# 3_0.net
KiCad netlist of a schematic drawn in EasyEDA
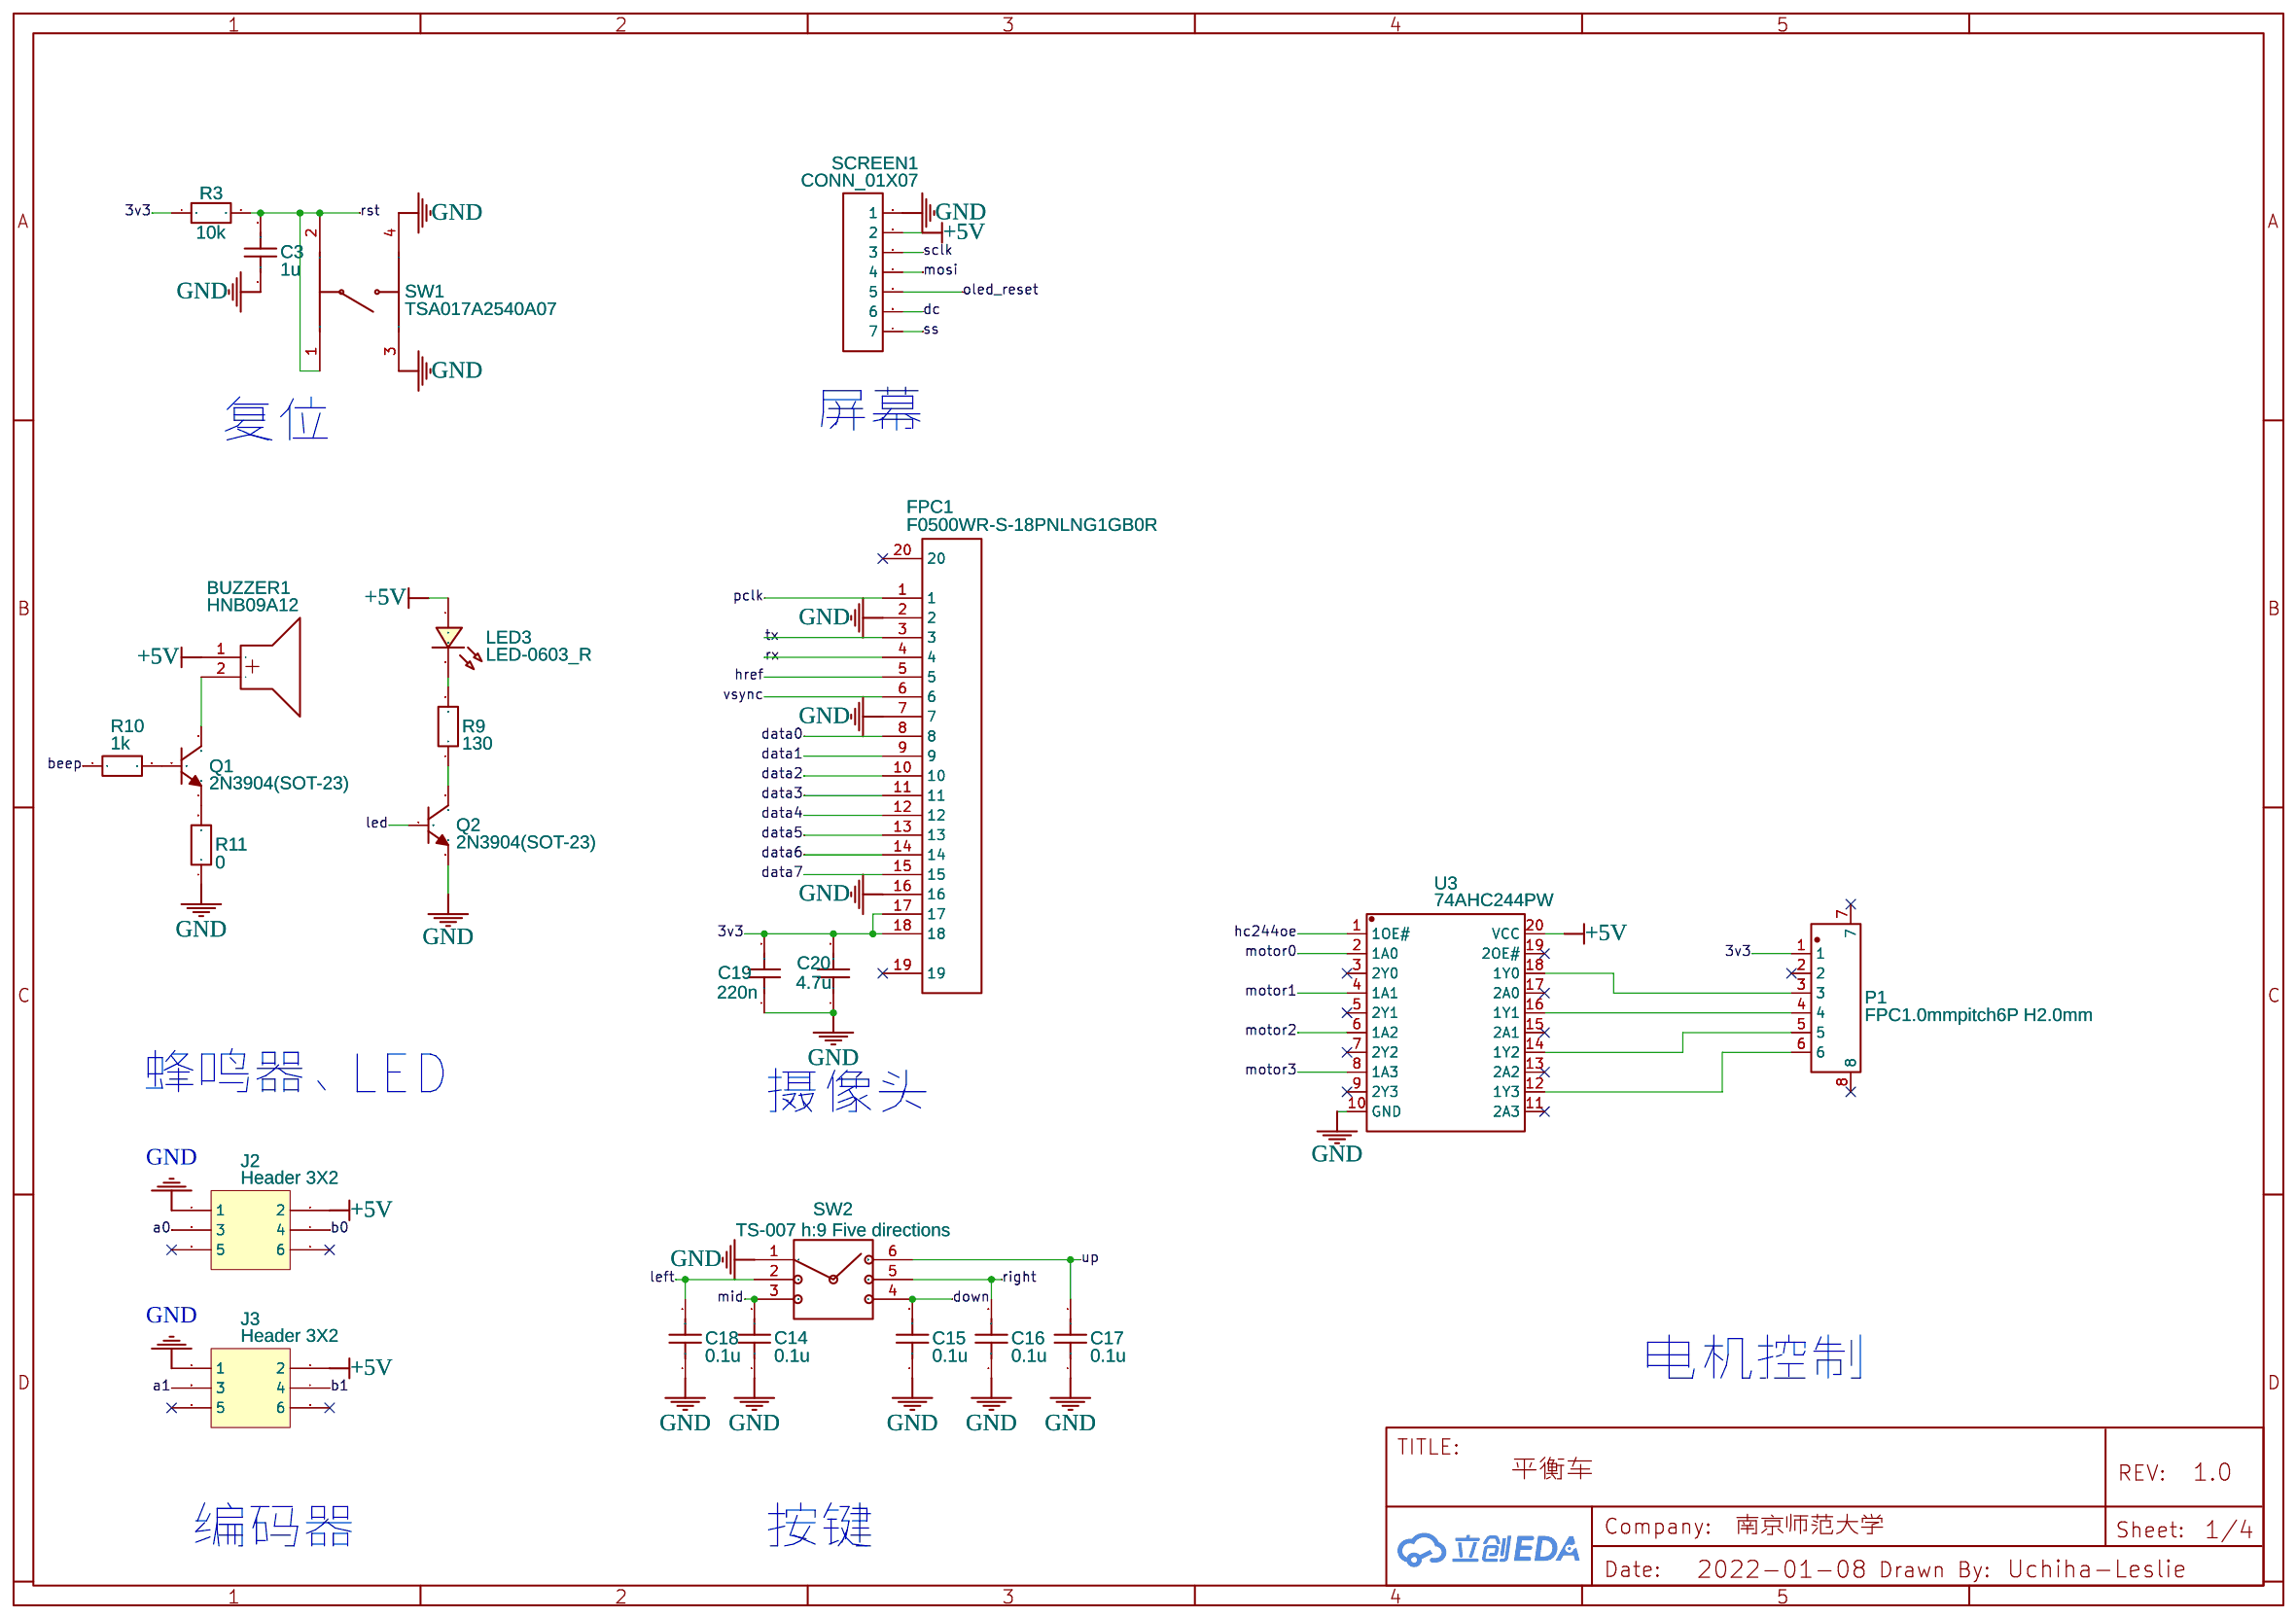
[diagram p0: Sheet_1]
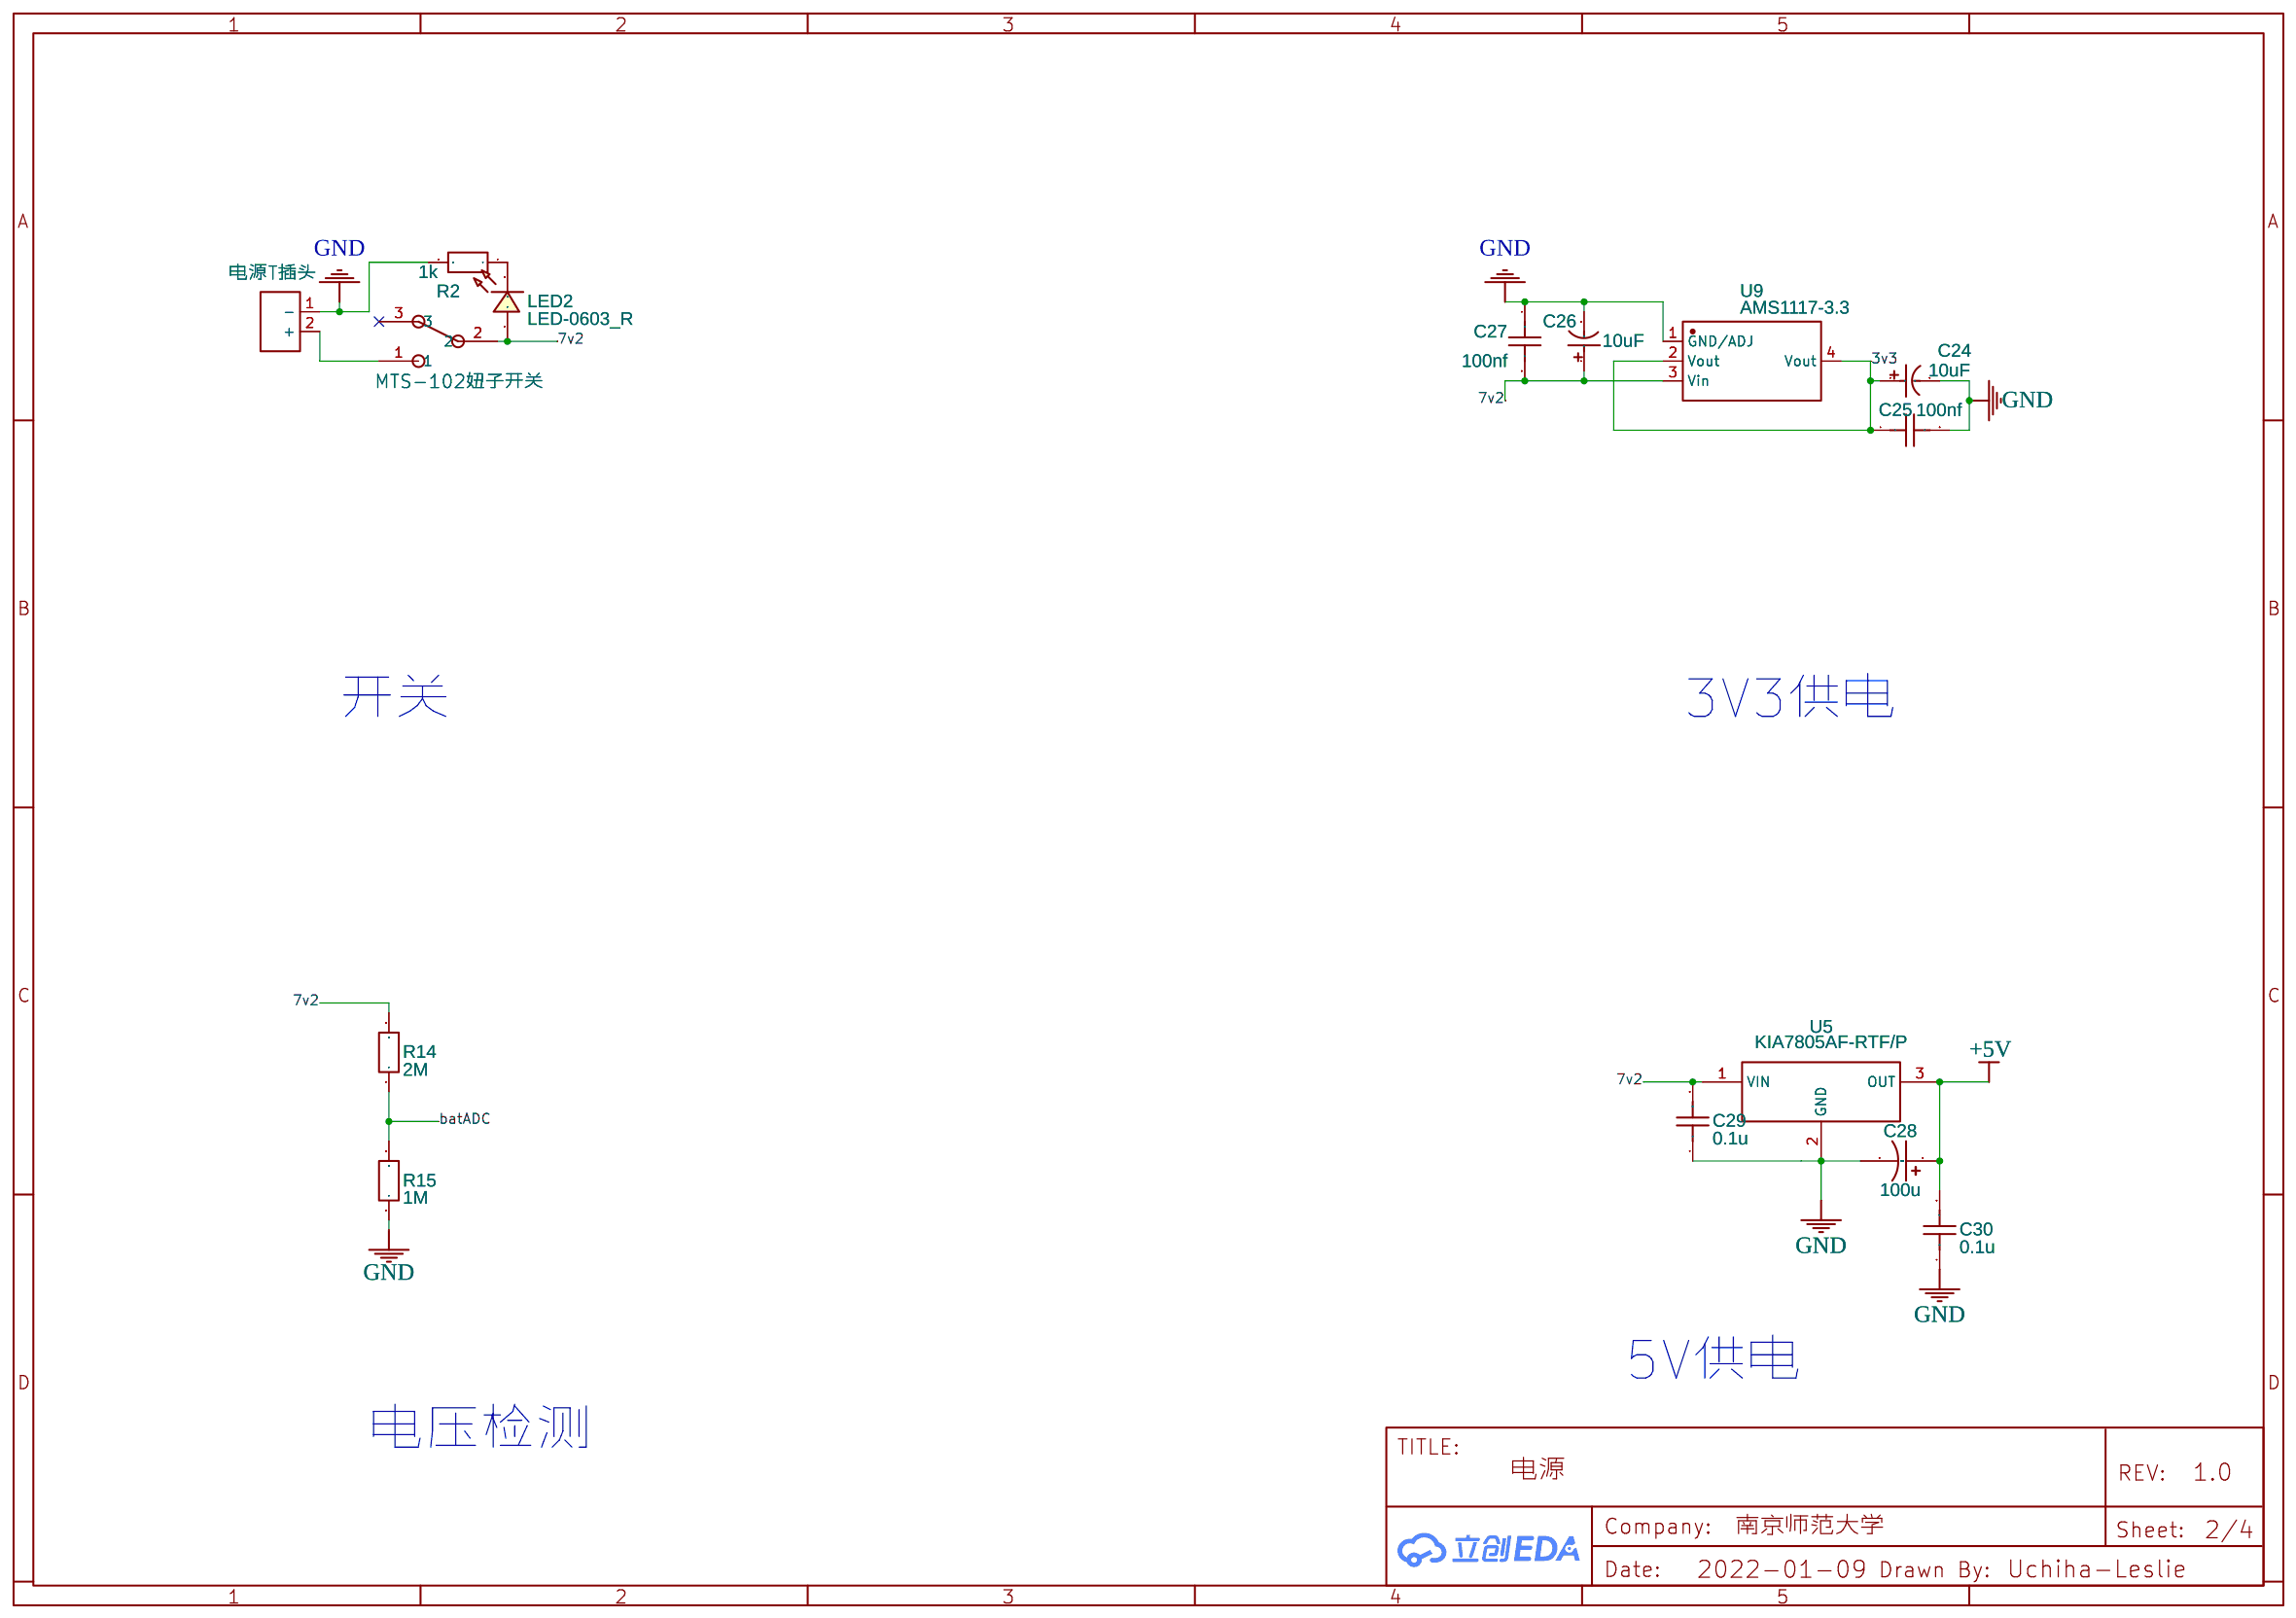
[diagram p1: 电源]
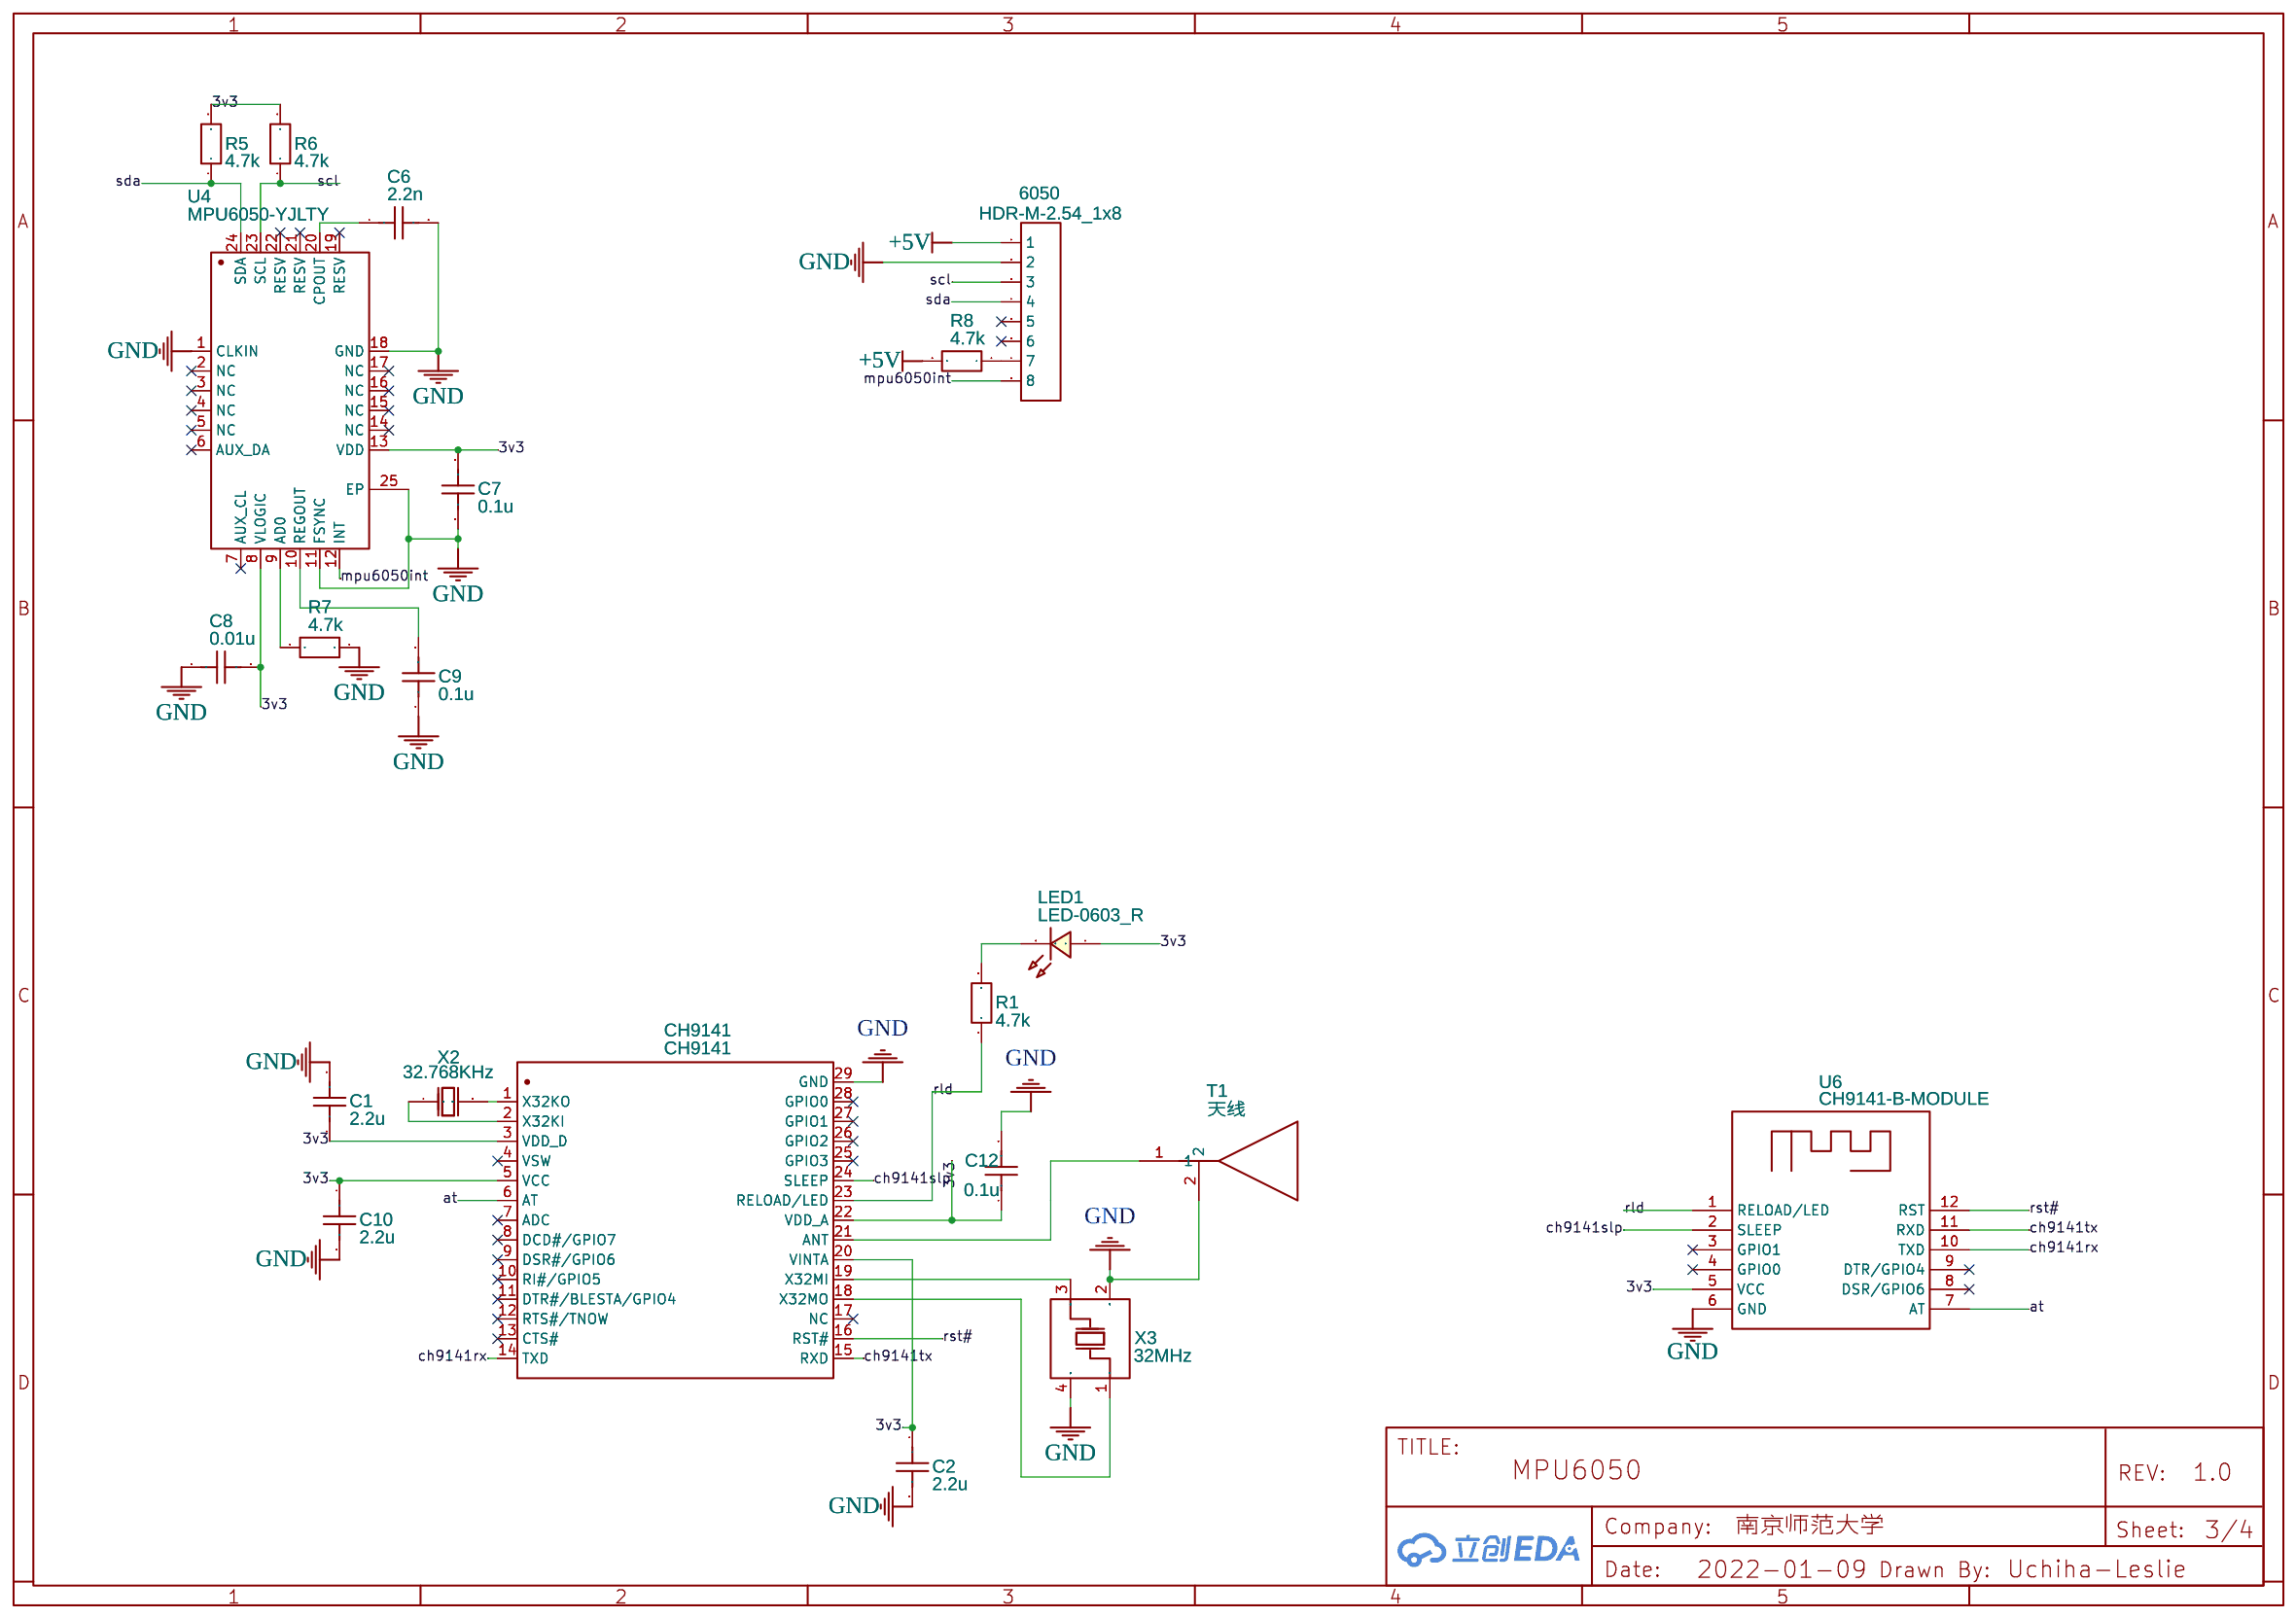
[diagram p2: MPU/蓝牙]
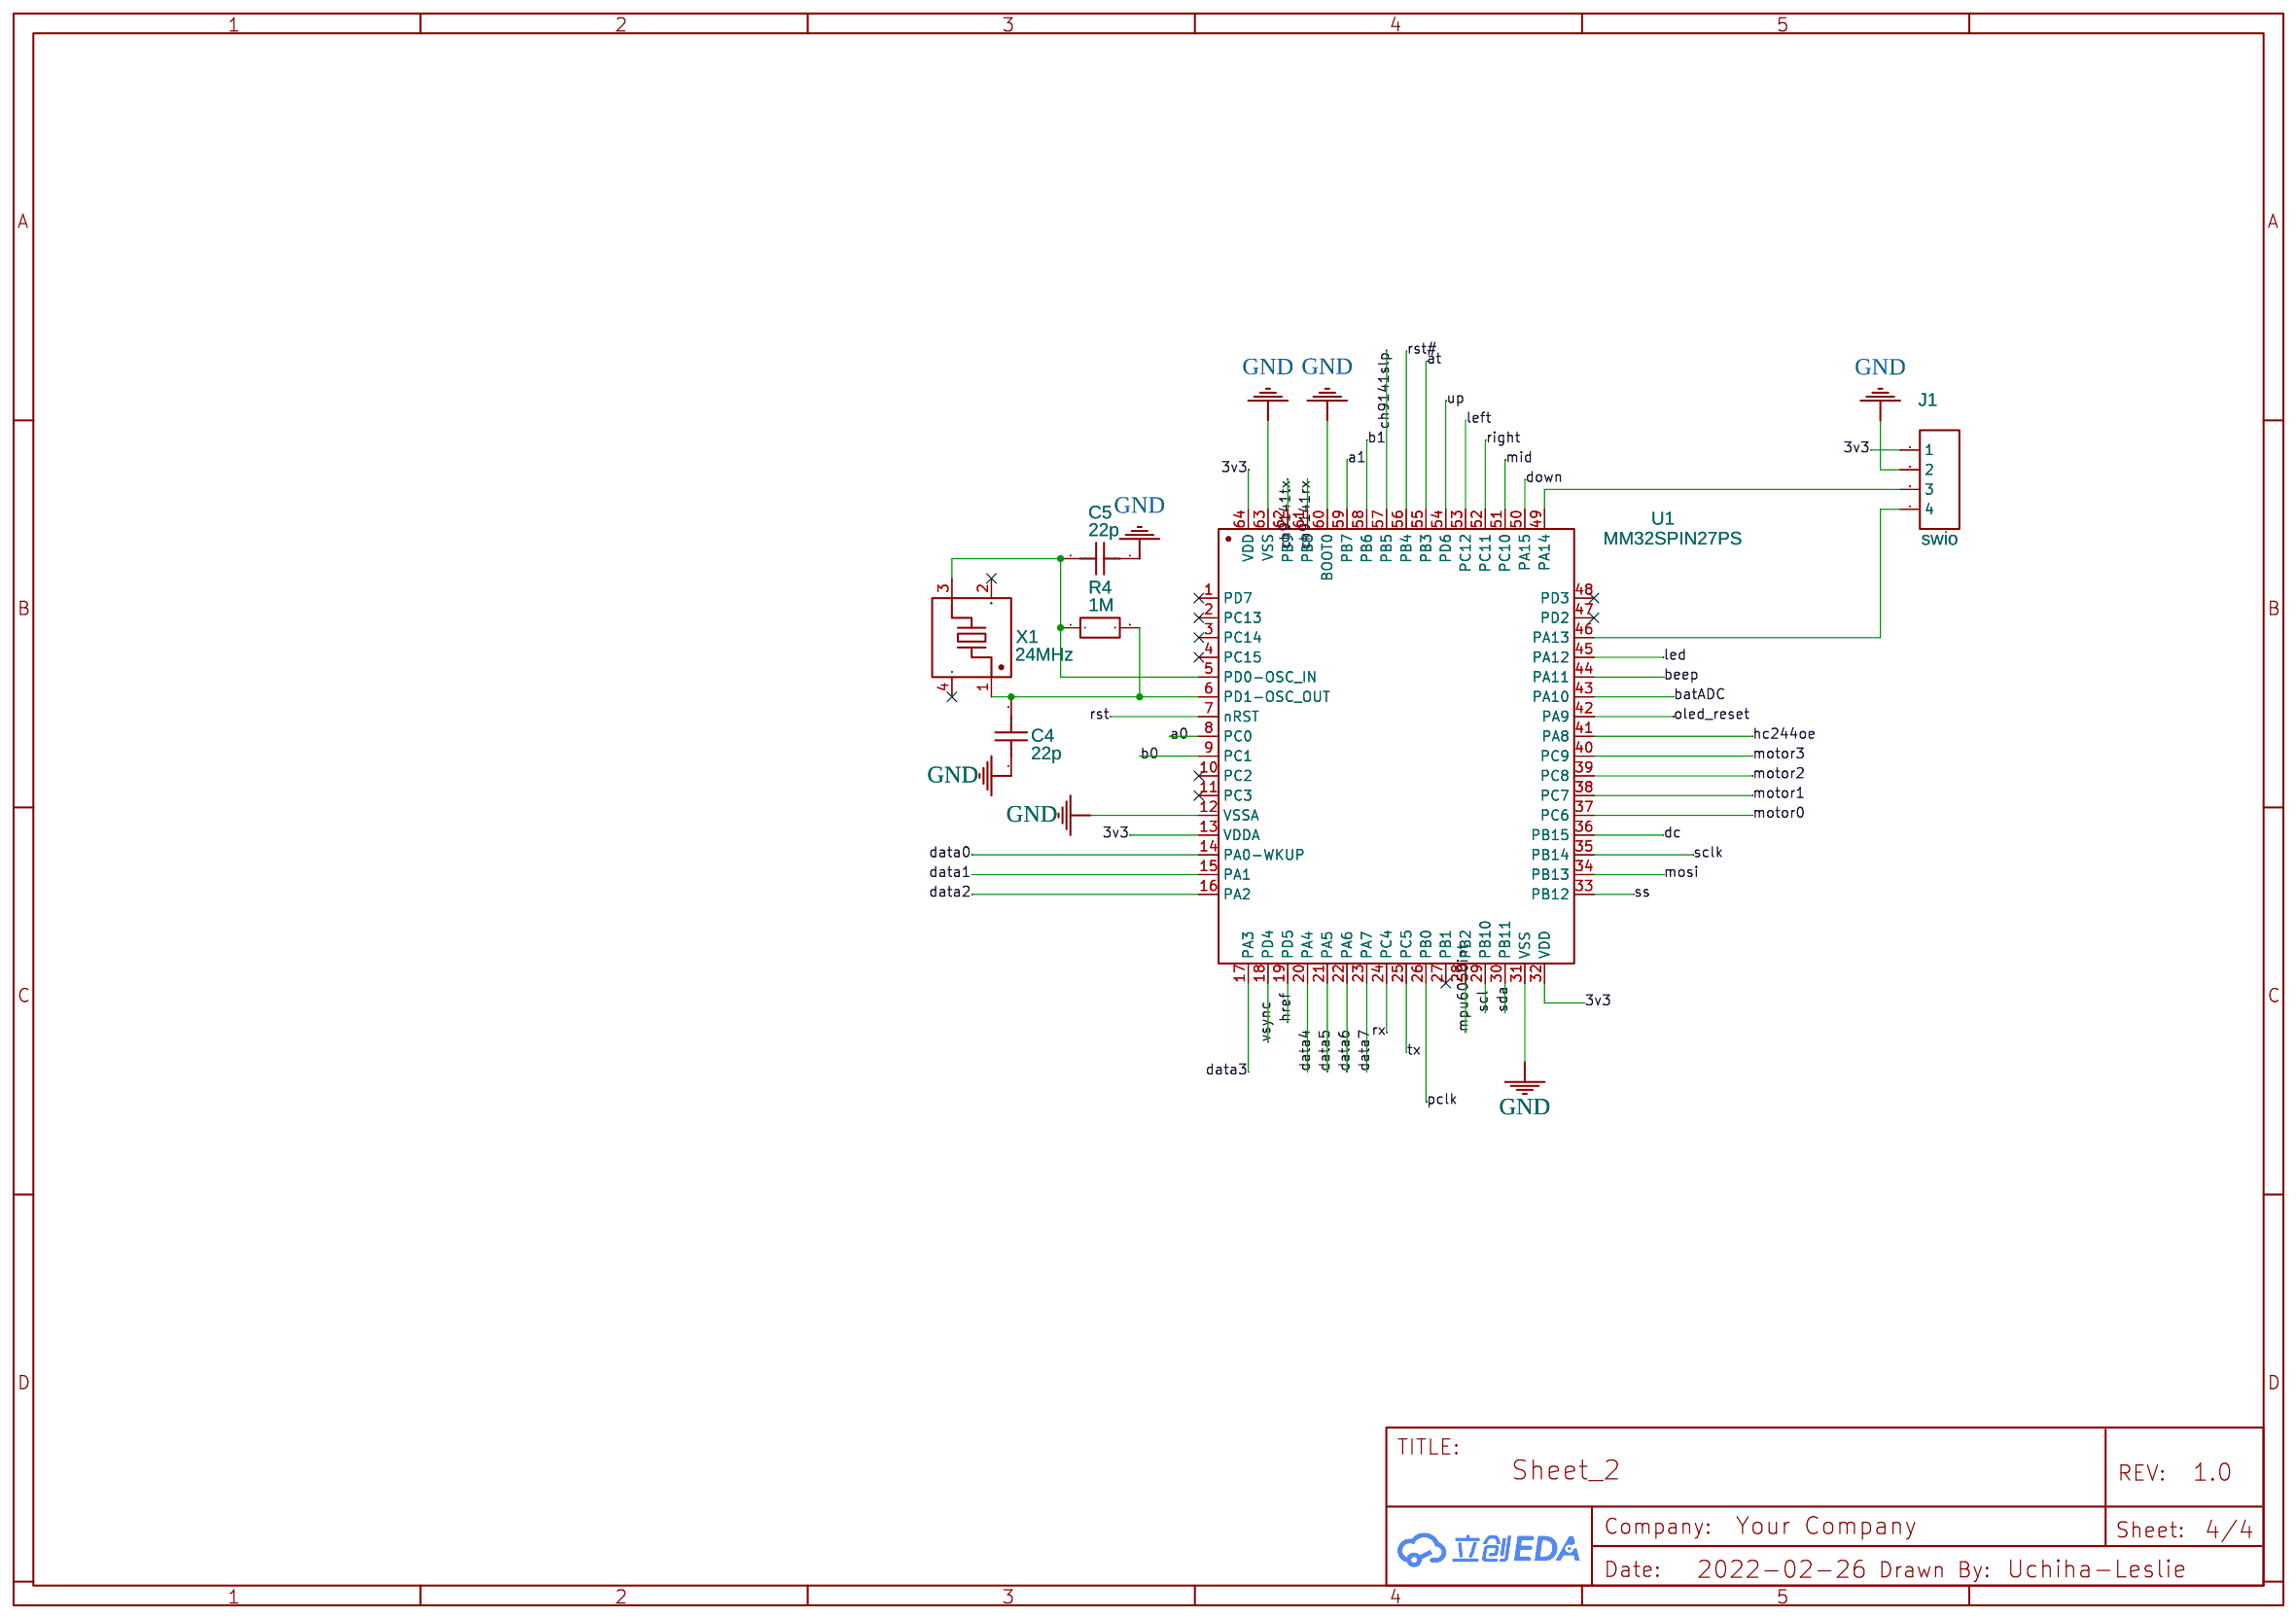
[diagram p3: MCU]

(export (version "E")
  (design (tool "Eeschema 10.0.6"))
  (components
    (comp (ref "BUZZER1")
      (value "HNB09A12")
      (fields (field (name "BOM_Supplier Part") "C122600"))
      (libsource (lib "") (part "HNB09A12"))
    )
    (comp (ref "C3") (value "1u") (libsource (lib "") (part "C_0603_US")))
    (comp (ref "C14") (value "0.1u") (libsource (lib "") (part "C_0603_US")))
    (comp (ref "C15") (value "0.1u") (libsource (lib "") (part "C_0603_US")))
    (comp (ref "C16") (value "0.1u") (libsource (lib "") (part "C_0603_US")))
    (comp (ref "C17") (value "0.1u") (libsource (lib "") (part "C_0603_US")))
    (comp (ref "C18") (value "0.1u") (libsource (lib "") (part "C_0603_US")))
    (comp (ref "C19") (value "220n") (libsource (lib "") (part "C_0603_US")))
    (comp (ref "C20") (value "4.7u") (libsource (lib "") (part "C_0603_US")))
    (comp (ref "FPC1")
      (value "F0500WR-S-18PNLNG1GB0R")
      (fields (field (name "BOM_Supplier Part") "C247896"))
      (libsource (lib "") (part "F0500WR-S-18PNLNG1GB0R"))
    )
    (comp (ref "J2") (value "Header 3X2") (libsource (lib "") (part "Header 3X2")))
    (comp (ref "J3") (value "Header 3X2") (libsource (lib "") (part "Header 3X2")))
    (comp (ref "LED3")
      (value "LED-0603_R")
      (fields
        (field (name "BOM_Manufacturer Part") "19-217/R6C-AL1M2VY/3T")
        (field (name "BOM_Supplier Part") "C72044")
      )
      (libsource (lib "") (part "LED-0603_R"))
    )
    (comp (ref "P1")
      (value "FPC1.0mmpitch6P H2.0mm")
      (fields
        (field (name "BOM_Manufacturer Part") "FPC1.0mmpitch6P H2.0mm翻盖式下接式")
        (field (name "BOM_Supplier Part") "C29804")
      )
      (libsource (lib "") (part "FPC1.0mmpitch6P H2.0mm"))
    )
    (comp (ref "Q1")
      (value "2N3904(SOT-23)")
      (fields
        (field (name "BOM_Manufacturer Part") "2n3904S-RTK/PS")
        (field (name "BOM_Supplier Part") "C18536")
      )
      (libsource (lib "") (part "2N3904(SOT-23)"))
    )
    (comp (ref "Q2")
      (value "2N3904(SOT-23)")
      (fields
        (field (name "BOM_Manufacturer Part") "2n3904S-RTK/PS")
        (field (name "BOM_Supplier Part") "C18536")
      )
      (libsource (lib "") (part "2N3904(SOT-23)"))
    )
    (comp (ref "R3") (value "10k") (libsource (lib "") (part "R_0603_EU")))
    (comp (ref "R9") (value "130") (libsource (lib "") (part "R_0603_EU_1")))
    (comp (ref "R10") (value "1k") (libsource (lib "") (part "R_0603_EU")))
    (comp (ref "R11") (value "0") (libsource (lib "") (part "R_0603_EU_1")))
    (comp (ref "SCREEN1") (value "CONN_01X07") (libsource (lib "") (part "CONN_01X07")))
    (comp (ref "SW1")
      (value "TSA017A2540A07")
      (fields (field (name "BOM_Supplier Part") "C2888434"))
      (libsource (lib "") (part "TSA017A2540A07"))
    )
    (comp (ref "SW2")
      (value "TS-007 h:9 Five directions")
      (fields (field (name "BOM_Supplier Part") "C3679"))
      (libsource (lib "") (part "TS-007 h{colon}9 Five directions"))
    )
    (comp (ref "U3")
      (value "74AHC244PW")
      (fields (field (name "BOM_Supplier Part") "C5515"))
      (libsource (lib "") (part "74AHC244PW"))
    )
    (comp (ref "C24")
      (value "10uF")
      (fields
        (field (name "BOM_Manufacturer Part") "10uF 16V 3*5")
        (field (name "BOM_Supplier Part") "C43798")
      )
      (libsource (lib "") (part "10uF 16V 3*5_1"))
    )
    (comp (ref "C25") (value "100nf") (libsource (lib "") (part "C_0603_US_2")))
    (comp (ref "C26")
      (value "10uF")
      (fields
        (field (name "BOM_Manufacturer Part") "10uF 16V 3*5")
        (field (name "BOM_Supplier Part") "C43798")
      )
      (libsource (lib "") (part "10uF 16V 3*5"))
    )
    (comp (ref "C27") (value "100nf") (libsource (lib "") (part "C_0603_US")))
    (comp (ref "C28") (value "100u") (libsource (lib "") (part "CE_TH_D8.0×F3.5_US")))
    (comp (ref "C29") (value "0.1u") (libsource (lib "") (part "C_0603_US_1")))
    (comp (ref "C30") (value "0.1u") (libsource (lib "") (part "C_0603_US_1")))
    (comp (ref "H1")
      (value "电源T插头")
      (fields (field (name "BOM_Manufacturer Part") "3-644456-2") (field (name "BOM_Supplier Part") "C90288"))
      (libsource (lib "") (part "电源T插头"))
    )
    (comp (ref "LED2")
      (value "LED-0603_R")
      (fields
        (field (name "BOM_Manufacturer Part") "19-217/R6C-AL1M2VY/3T")
        (field (name "BOM_Supplier Part") "C72044")
      )
      (libsource (lib "") (part "LED-0603_R"))
    )
    (comp (ref "R2") (value "1k") (libsource (lib "") (part "R_0603_EU")))
    (comp (ref "R14") (value "2M") (libsource (lib "") (part "R_0603_EU_1")))
    (comp (ref "R15") (value "1M") (libsource (lib "") (part "R_0603_EU_1")))
    (comp (ref "U2") (value "MTS-102妞子开关") (libsource (lib "") (part "MTS-102妞子开关")))
    (comp (ref "U5")
      (value "KIA7805AF-RTF/P")
      (fields (field (name "BOM_Supplier Part") "C69755"))
      (libsource (lib "") (part "KIA7805AF-RTF/P"))
    )
    (comp (ref "U9")
      (value "AMS1117-3.3")
      (fields (field (name "BOM_Supplier Part") "C6186"))
      (libsource (lib "") (part "AMS1117-3.3"))
    )
    (comp (ref "6050")
      (value "HDR-M-2.54_1x8")
      (fields (field (name "BOM_Supplier Part") "C190820"))
      (libsource (lib "") (part "HDR-M-2.54_1x8"))
    )
    (comp (ref "C1") (value "2.2u") (libsource (lib "") (part "C_0603_US")))
    (comp (ref "C2") (value "2.2u") (libsource (lib "") (part "C_0603_US_2")))
    (comp (ref "C6") (value "2.2n") (libsource (lib "") (part "C_0603_US_1")))
    (comp (ref "C7") (value "0.1u") (libsource (lib "") (part "C_0603_US")))
    (comp (ref "C8") (value "0.01u") (libsource (lib "") (part "C_0603_US_1")))
    (comp (ref "C9") (value "0.1u") (libsource (lib "") (part "C_0603_US")))
    (comp (ref "C10") (value "2.2u") (libsource (lib "") (part "C_0603_US_2")))
    (comp (ref "C12") (value "0.1u") (libsource (lib "") (part "C_0603_US")))
    (comp (ref "CH9141")
      (value "CH9141")
      (fields (field (name "BOM_Supplier Part") "C2693433"))
      (libsource (lib "") (part "CH9141"))
    )
    (comp (ref "LED1")
      (value "LED-0603_R")
      (fields
        (field (name "BOM_Manufacturer Part") "19-217/R6C-AL1M2VY/3T")
        (field (name "BOM_Supplier Part") "C72044")
      )
      (libsource (lib "") (part "LED-0603_R"))
    )
    (comp (ref "R1") (value "4.7k") (libsource (lib "") (part "R_0603_EU_1")))
    (comp (ref "R5") (value "4.7k") (libsource (lib "") (part "R_0603_EU_1")))
    (comp (ref "R6") (value "4.7k") (libsource (lib "") (part "R_0603_EU_1")))
    (comp (ref "R7") (value "4.7k") (libsource (lib "") (part "R_0603_EU")))
    (comp (ref "R8") (value "4.7k") (libsource (lib "") (part "R_0603_EU")))
    (comp (ref "T1") (value "天线") (libsource (lib "") (part "天线")))
    (comp (ref "U4")
      (value "MPU6050-YJLTY")
      (fields (field (name "BOM_Supplier Part") "C2912107"))
      (libsource (lib "") (part "MPU6050-YJLTY"))
    )
    (comp (ref "U6") (value "CH9141-B-MODULE") (libsource (lib "") (part "CH9141-B-MODULE")))
    (comp (ref "X2")
      (value "32.768KHz")
      (fields
        (field (name "BOM_Manufacturer Part") "ABS07-32.768KHZ-9-T")
        (field (name "BOM_Supplier Part") "C179635")
      )
      (libsource (lib "") (part "ABS07-32.768KHZ-9-T"))
    )
    (comp (ref "X3")
      (value "32MHz")
      (fields
        (field (name "BOM_Manufacturer Part") "M32000TC142")
        (field (name "BOM_Supplier Part") "C280076")
      )
      (libsource (lib "") (part "M32000TC142"))
    )
    (comp (ref "C4") (value "22p") (libsource (lib "") (part "C_0603_US_1")))
    (comp (ref "C5") (value "22p") (libsource (lib "") (part "C_0603_US")))
    (comp (ref "J1")
      (value "swio")
      (fields (field (name "BOM_Supplier Part") "C124378"))
      (libsource (lib "") (part "HDR-M-2.54_1x4"))
    )
    (comp (ref "R4") (value "1M") (libsource (lib "") (part "R_0603_EU")))
    (comp (ref "U1")
      (value "MM32SPIN27PS")
      (fields
        (field (name "BOM_Manufacturer Part") "mm32spin27ps")
        (field (name "BOM_Supplier Part") "C2908053")
      )
      (libsource (lib "") (part "MM32SPIN27PS"))
    )
    (comp (ref "X1")
      (value "24MHz")
      (fields
        (field (name "BOM_Manufacturer Part") "CN4024M00012T8188012")
        (field (name "BOM_Supplier Part") "C708987")
      )
      (libsource (lib "") (part "CN4024M00012T8188012"))
    )
  )
  (nets
    (net (code "1") (name "+5V") (class "Default")
      (node (ref "6050") (pin "1") (pinfunction "1_1") (pintype "unspecified"))
      (node (ref "BUZZER1") (pin "1") (pinfunction "+_1") (pintype "unspecified"))
      (node (ref "C28") (pin "1") (pinfunction "1_1") (pintype "unspecified"))
      (node (ref "C30") (pin "2") (pinfunction "2_2") (pintype "unspecified"))
      (node (ref "J2") (pin "2") (pinfunction "2_2") (pintype "unspecified"))
      (node (ref "J3") (pin "2") (pinfunction "2_2") (pintype "unspecified"))
      (node (ref "LED3") (pin "1") (pinfunction "1_1") (pintype "unspecified"))
      (node (ref "R8") (pin "2") (pinfunction "2_2") (pintype "unspecified"))
      (node (ref "SCREEN1") (pin "2") (pinfunction "2_2") (pintype "input"))
      (node (ref "U3") (pin "20") (pinfunction "VCC_20") (pintype "unspecified"))
      (node (ref "U5") (pin "3") (pinfunction "OUT_3") (pintype "unspecified"))
    )
    (net (code "2") (name "3v3") (class "Default")
      (node (ref "C1") (pin "1") (pinfunction "1_1") (pintype "unspecified"))
      (node (ref "C10") (pin "1") (pinfunction "1_1") (pintype "unspecified"))
      (node (ref "C12") (pin "1") (pinfunction "1_1") (pintype "unspecified"))
      (node (ref "C19") (pin "2") (pinfunction "2_2") (pintype "unspecified"))
      (node (ref "C2") (pin "1") (pinfunction "1_1") (pintype "unspecified"))
      (node (ref "C20") (pin "2") (pinfunction "2_2") (pintype "unspecified"))
      (node (ref "C24") (pin "1") (pinfunction "1_1") (pintype "input"))
      (node (ref "C25") (pin "1") (pinfunction "1_1") (pintype "unspecified"))
      (node (ref "C7") (pin "2") (pinfunction "2_2") (pintype "unspecified"))
      (node (ref "C8") (pin "2") (pinfunction "2_2") (pintype "unspecified"))
      (node (ref "CH9141") (pin "20") (pinfunction "VINTA_20") (pintype "unspecified"))
      (node (ref "CH9141") (pin "22") (pinfunction "VDD_A_22") (pintype "unspecified"))
      (node (ref "CH9141") (pin "3") (pinfunction "VDD_D_3") (pintype "unspecified"))
      (node (ref "CH9141") (pin "5") (pinfunction "VCC_5") (pintype "unspecified"))
      (node (ref "FPC1") (pin "17") (pinfunction "17_17") (pintype "unspecified"))
      (node (ref "FPC1") (pin "18") (pinfunction "18_18") (pintype "unspecified"))
      (node (ref "J1") (pin "1") (pinfunction "1_1") (pintype "unspecified"))
      (node (ref "LED1") (pin "1") (pinfunction "1_1") (pintype "unspecified"))
      (node (ref "P1") (pin "1") (pinfunction "1_1") (pintype "unspecified"))
      (node (ref "R3") (pin "1") (pinfunction "1_1") (pintype "unspecified"))
      (node (ref "R5") (pin "2") (pinfunction "2_2") (pintype "unspecified"))
      (node (ref "R6") (pin "2") (pinfunction "2_2") (pintype "unspecified"))
      (node (ref "U1") (pin "13") (pinfunction "VDDA_13") (pintype "unspecified"))
      (node (ref "U1") (pin "32") (pinfunction "VDD_32") (pintype "unspecified"))
      (node (ref "U1") (pin "64") (pinfunction "VDD_64") (pintype "unspecified"))
      (node (ref "U4") (pin "13") (pinfunction "VDD_13") (pintype "unspecified"))
      (node (ref "U4") (pin "8") (pinfunction "VLOGIC_8") (pintype "unspecified"))
      (node (ref "U6") (pin "5") (pinfunction "VCC_5") (pintype "unspecified"))
      (node (ref "U9") (pin "2") (pinfunction "Vout_2") (pintype "unspecified"))
      (node (ref "U9") (pin "4") (pinfunction "Vout_4") (pintype "unspecified"))
    )
    (net (code "3") (name "7v2") (class "Default")
      (node (ref "C26") (pin "1") (pinfunction "1_1") (pintype "input"))
      (node (ref "C27") (pin "2") (pinfunction "2_2") (pintype "unspecified"))
      (node (ref "C29") (pin "2") (pinfunction "2_2") (pintype "unspecified"))
      (node (ref "LED2") (pin "1") (pinfunction "1_1") (pintype "unspecified"))
      (node (ref "R14") (pin "2") (pinfunction "2_2") (pintype "unspecified"))
      (node (ref "U2") (pin "2") (pinfunction "2_2") (pintype "unspecified"))
      (node (ref "U5") (pin "1") (pinfunction "VIN_1") (pintype "input"))
      (node (ref "U9") (pin "3") (pinfunction "Vin_3") (pintype "unspecified"))
    )
    (net (code "4") (name "GND") (class "Default")
      (node (ref "6050") (pin "2") (pinfunction "2_2") (pintype "unspecified"))
      (node (ref "C1") (pin "2") (pinfunction "2_2") (pintype "unspecified"))
      (node (ref "C10") (pin "2") (pinfunction "2_2") (pintype "unspecified"))
      (node (ref "C12") (pin "2") (pinfunction "2_2") (pintype "unspecified"))
      (node (ref "C14") (pin "1") (pinfunction "1_1") (pintype "unspecified"))
      (node (ref "C15") (pin "1") (pinfunction "1_1") (pintype "unspecified"))
      (node (ref "C16") (pin "1") (pinfunction "1_1") (pintype "unspecified"))
      (node (ref "C17") (pin "1") (pinfunction "1_1") (pintype "unspecified"))
      (node (ref "C18") (pin "1") (pinfunction "1_1") (pintype "unspecified"))
      (node (ref "C19") (pin "1") (pinfunction "1_1") (pintype "unspecified"))
      (node (ref "C2") (pin "2") (pinfunction "2_2") (pintype "unspecified"))
      (node (ref "C20") (pin "1") (pinfunction "1_1") (pintype "unspecified"))
      (node (ref "C24") (pin "2") (pinfunction "2_2") (pintype "input"))
      (node (ref "C25") (pin "2") (pinfunction "2_2") (pintype "unspecified"))
      (node (ref "C26") (pin "2") (pinfunction "2_2") (pintype "input"))
      (node (ref "C27") (pin "1") (pinfunction "1_1") (pintype "unspecified"))
      (node (ref "C28") (pin "2") (pinfunction "2_2") (pintype "unspecified"))
      (node (ref "C29") (pin "1") (pinfunction "1_1") (pintype "unspecified"))
      (node (ref "C3") (pin "1") (pinfunction "1_1") (pintype "unspecified"))
      (node (ref "C30") (pin "1") (pinfunction "1_1") (pintype "unspecified"))
      (node (ref "C4") (pin "1") (pinfunction "1_1") (pintype "unspecified"))
      (node (ref "C5") (pin "1") (pinfunction "1_1") (pintype "unspecified"))
      (node (ref "C6") (pin "2") (pinfunction "2_2") (pintype "unspecified"))
      (node (ref "C7") (pin "1") (pinfunction "1_1") (pintype "unspecified"))
      (node (ref "C8") (pin "1") (pinfunction "1_1") (pintype "unspecified"))
      (node (ref "C9") (pin "1") (pinfunction "1_1") (pintype "unspecified"))
      (node (ref "CH9141") (pin "29") (pinfunction "GND_29") (pintype "unspecified"))
      (node (ref "FPC1") (pin "16") (pinfunction "16_16") (pintype "unspecified"))
      (node (ref "FPC1") (pin "2") (pinfunction "2_2") (pintype "unspecified"))
      (node (ref "FPC1") (pin "7") (pinfunction "7_7") (pintype "unspecified"))
      (node (ref "H1") (pin "1") (pinfunction "-_1") (pintype "unspecified"))
      (node (ref "J1") (pin "2") (pinfunction "2_2") (pintype "unspecified"))
      (node (ref "J2") (pin "1") (pinfunction "1_1") (pintype "unspecified"))
      (node (ref "J3") (pin "1") (pinfunction "1_1") (pintype "unspecified"))
      (node (ref "Q2") (pin "1") (pinfunction "E_1") (pintype "input"))
      (node (ref "R11") (pin "1") (pinfunction "1_1") (pintype "unspecified"))
      (node (ref "R15") (pin "1") (pinfunction "1_1") (pintype "unspecified"))
      (node (ref "R2") (pin "2") (pinfunction "2_2") (pintype "unspecified"))
      (node (ref "R7") (pin "1") (pinfunction "1_1") (pintype "unspecified"))
      (node (ref "SCREEN1") (pin "1") (pinfunction "1_1") (pintype "input"))
      (node (ref "SW1") (pin "3") (pinfunction "3_3") (pintype "unspecified"))
      (node (ref "SW1") (pin "4") (pinfunction "4_4") (pintype "unspecified"))
      (node (ref "SW2") (pin "1") (pinfunction "1_1") (pintype "input"))
      (node (ref "T1") (pin "2") (pinfunction "2_2") (pintype "unspecified"))
      (node (ref "U1") (pin "12") (pinfunction "VSSA_12") (pintype "unspecified"))
      (node (ref "U1") (pin "31") (pinfunction "VSS_31") (pintype "unspecified"))
      (node (ref "U1") (pin "60") (pinfunction "BOOT0_60") (pintype "unspecified"))
      (node (ref "U1") (pin "63") (pinfunction "VSS_63") (pintype "unspecified"))
      (node (ref "U3") (pin "10") (pinfunction "GND_10") (pintype "unspecified"))
      (node (ref "U4") (pin "1") (pinfunction "CLKIN_1") (pintype "unspecified"))
      (node (ref "U4") (pin "11") (pinfunction "FSYNC_11") (pintype "unspecified"))
      (node (ref "U4") (pin "18") (pinfunction "GND_18") (pintype "unspecified"))
      (node (ref "U4") (pin "25") (pinfunction "EP_25") (pintype "unspecified"))
      (node (ref "U5") (pin "2") (pinfunction "GND_2") (pintype "unspecified"))
      (node (ref "U6") (pin "6") (pinfunction "GND_6") (pintype "unspecified"))
      (node (ref "U9") (pin "1") (pinfunction "GND/ADJ_1") (pintype "unspecified"))
      (node (ref "X3") (pin "2") (pinfunction "GND_2") (pintype "unspecified"))
      (node (ref "X3") (pin "4") (pinfunction "GND_4") (pintype "unspecified"))
    )
    (net (code "5") (name "Net-(6050-Pad7)") (class "Default")
      (node (ref "6050") (pin "7") (pinfunction "7_7") (pintype "unspecified"))
      (node (ref "R8") (pin "1") (pinfunction "1_1") (pintype "unspecified"))
    )
    (net (code "6") (name "Net-(BUZZER1--)") (class "Default")
      (node (ref "BUZZER1") (pin "2") (pinfunction "-_2") (pintype "unspecified"))
      (node (ref "Q1") (pin "3") (pinfunction "C_3") (pintype "input"))
    )
    (net (code "7") (name "Net-(CH9141-ANT)") (class "Default")
      (node (ref "CH9141") (pin "21") (pinfunction "ANT_21") (pintype "unspecified"))
      (node (ref "T1") (pin "1") (pinfunction "1_1") (pintype "unspecified"))
    )
    (net (code "8") (name "Net-(CH9141-X32KI)") (class "Default")
      (node (ref "CH9141") (pin "2") (pinfunction "X32KI_2") (pintype "unspecified"))
      (node (ref "X2") (pin "1") (pinfunction "OSC1_1") (pintype "input"))
    )
    (net (code "9") (name "Net-(CH9141-X32KO)") (class "Default")
      (node (ref "CH9141") (pin "1") (pinfunction "X32KO_1") (pintype "unspecified"))
      (node (ref "X2") (pin "2") (pinfunction "OSC2_2") (pintype "input"))
    )
    (net (code "10") (name "Net-(CH9141-X32MI)") (class "Default")
      (node (ref "CH9141") (pin "19") (pinfunction "X32MI_19") (pintype "unspecified"))
      (node (ref "X3") (pin "3") (pinfunction "OSC2_3") (pintype "unspecified"))
    )
    (net (code "11") (name "Net-(CH9141-X32MO)") (class "Default")
      (node (ref "CH9141") (pin "18") (pinfunction "X32MO_18") (pintype "unspecified"))
      (node (ref "X3") (pin "1") (pinfunction "OSC1_1") (pintype "unspecified"))
    )
    (net (code "12") (name "Net-(H1-+)") (class "Default")
      (node (ref "H1") (pin "2") (pinfunction "+_2") (pintype "unspecified"))
      (node (ref "U2") (pin "1") (pinfunction "1_1") (pintype "unspecified"))
    )
    (net (code "13") (name "Net-(LED1-Pad2)") (class "Default")
      (node (ref "LED1") (pin "2") (pinfunction "2_2") (pintype "unspecified"))
      (node (ref "R1") (pin "2") (pinfunction "2_2") (pintype "unspecified"))
    )
    (net (code "14") (name "Net-(LED2-Pad2)") (class "Default")
      (node (ref "LED2") (pin "2") (pinfunction "2_2") (pintype "unspecified"))
      (node (ref "R2") (pin "1") (pinfunction "1_1") (pintype "unspecified"))
    )
    (net (code "15") (name "Net-(LED3-Pad2)") (class "Default")
      (node (ref "LED3") (pin "2") (pinfunction "2_2") (pintype "unspecified"))
      (node (ref "R9") (pin "2") (pinfunction "2_2") (pintype "unspecified"))
    )
    (net (code "16") (name "Net-(Q1-B)") (class "Default")
      (node (ref "Q1") (pin "2") (pinfunction "B_2") (pintype "input"))
      (node (ref "R10") (pin "2") (pinfunction "2_2") (pintype "unspecified"))
    )
    (net (code "17") (name "Net-(Q1-E)") (class "Default")
      (node (ref "Q1") (pin "1") (pinfunction "E_1") (pintype "input"))
      (node (ref "R11") (pin "2") (pinfunction "2_2") (pintype "unspecified"))
    )
    (net (code "18") (name "Net-(Q2-C)") (class "Default")
      (node (ref "Q2") (pin "3") (pinfunction "C_3") (pintype "input"))
      (node (ref "R9") (pin "1") (pinfunction "1_1") (pintype "unspecified"))
    )
    (net (code "19") (name "Net-(U1-PA13)") (class "Default")
      (node (ref "J1") (pin "4") (pinfunction "4_4") (pintype "unspecified"))
      (node (ref "U1") (pin "46") (pinfunction "PA13_46") (pintype "unspecified"))
    )
    (net (code "20") (name "Net-(U1-PA14)") (class "Default")
      (node (ref "J1") (pin "3") (pinfunction "3_3") (pintype "unspecified"))
      (node (ref "U1") (pin "49") (pinfunction "PA14_49") (pintype "unspecified"))
    )
    (net (code "21") (name "Net-(U1-PD0-OSC_IN)") (class "Default")
      (node (ref "C5") (pin "2") (pinfunction "2_2") (pintype "unspecified"))
      (node (ref "R4") (pin "1") (pinfunction "1_1") (pintype "unspecified"))
      (node (ref "U1") (pin "5") (pinfunction "PD0-OSC_IN_5") (pintype "unspecified"))
      (node (ref "X1") (pin "3") (pinfunction "3_3") (pintype "input"))
    )
    (net (code "22") (name "Net-(U1-PD1-OSC_OUT)") (class "Default")
      (node (ref "C4") (pin "2") (pinfunction "2_2") (pintype "unspecified"))
      (node (ref "R4") (pin "2") (pinfunction "2_2") (pintype "unspecified"))
      (node (ref "U1") (pin "6") (pinfunction "PD1-OSC_OUT_6") (pintype "unspecified"))
      (node (ref "X1") (pin "1") (pinfunction "1_1") (pintype "input"))
    )
    (net (code "23") (name "Net-(U3-1Y0)") (class "Default")
      (node (ref "P1") (pin "3") (pinfunction "3_3") (pintype "unspecified"))
      (node (ref "U3") (pin "18") (pinfunction "1Y0_18") (pintype "unspecified"))
    )
    (net (code "24") (name "Net-(U3-1Y1)") (class "Default")
      (node (ref "P1") (pin "4") (pinfunction "4_4") (pintype "unspecified"))
      (node (ref "U3") (pin "16") (pinfunction "1Y1_16") (pintype "unspecified"))
    )
    (net (code "25") (name "Net-(U3-1Y2)") (class "Default")
      (node (ref "P1") (pin "5") (pinfunction "5_5") (pintype "unspecified"))
      (node (ref "U3") (pin "14") (pinfunction "1Y2_14") (pintype "unspecified"))
    )
    (net (code "26") (name "Net-(U3-1Y3)") (class "Default")
      (node (ref "P1") (pin "6") (pinfunction "6_6") (pintype "unspecified"))
      (node (ref "U3") (pin "12") (pinfunction "1Y3_12") (pintype "unspecified"))
    )
    (net (code "27") (name "Net-(U4-AD0)") (class "Default")
      (node (ref "R7") (pin "2") (pinfunction "2_2") (pintype "unspecified"))
      (node (ref "U4") (pin "9") (pinfunction "AD0_9") (pintype "unspecified"))
    )
    (net (code "28") (name "Net-(U4-CPOUT)") (class "Default")
      (node (ref "C6") (pin "1") (pinfunction "1_1") (pintype "unspecified"))
      (node (ref "U4") (pin "20") (pinfunction "CPOUT_20") (pintype "unspecified"))
    )
    (net (code "29") (name "Net-(U4-REGOUT)") (class "Default")
      (node (ref "C9") (pin "2") (pinfunction "2_2") (pintype "unspecified"))
      (node (ref "U4") (pin "10") (pinfunction "REGOUT_10") (pintype "unspecified"))
    )
    (net (code "30") (name "a0") (class "Default")
      (node (ref "J2") (pin "3") (pinfunction "3_3") (pintype "unspecified"))
      (node (ref "U1") (pin "8") (pinfunction "PC0_8") (pintype "unspecified"))
    )
    (net (code "31") (name "a1") (class "Default")
      (node (ref "J3") (pin "3") (pinfunction "3_3") (pintype "unspecified"))
      (node (ref "U1") (pin "59") (pinfunction "PB7_59") (pintype "unspecified"))
    )
    (net (code "32") (name "at") (class "Default")
      (node (ref "CH9141") (pin "6") (pinfunction "AT_6") (pintype "unspecified"))
      (node (ref "U1") (pin "55") (pinfunction "PB3_55") (pintype "unspecified"))
      (node (ref "U6") (pin "7") (pinfunction "AT_7") (pintype "unspecified"))
    )
    (net (code "33") (name "b0") (class "Default")
      (node (ref "J2") (pin "4") (pinfunction "4_4") (pintype "unspecified"))
      (node (ref "U1") (pin "9") (pinfunction "PC1_9") (pintype "unspecified"))
    )
    (net (code "34") (name "b1") (class "Default")
      (node (ref "J3") (pin "4") (pinfunction "4_4") (pintype "unspecified"))
      (node (ref "U1") (pin "58") (pinfunction "PB6_58") (pintype "unspecified"))
    )
    (net (code "35") (name "batADC") (class "Default")
      (node (ref "R14") (pin "1") (pinfunction "1_1") (pintype "unspecified"))
      (node (ref "R15") (pin "2") (pinfunction "2_2") (pintype "unspecified"))
      (node (ref "U1") (pin "43") (pinfunction "PA10_43") (pintype "unspecified"))
    )
    (net (code "36") (name "beep") (class "Default")
      (node (ref "R10") (pin "1") (pinfunction "1_1") (pintype "unspecified"))
      (node (ref "U1") (pin "44") (pinfunction "PA11_44") (pintype "unspecified"))
    )
    (net (code "37") (name "ch9141rx") (class "Default")
      (node (ref "CH9141") (pin "14") (pinfunction "TXD_14") (pintype "unspecified"))
      (node (ref "U1") (pin "61") (pinfunction "PB8_61") (pintype "unspecified"))
      (node (ref "U6") (pin "10") (pinfunction "TXD_10") (pintype "unspecified"))
    )
    (net (code "38") (name "ch9141slp") (class "Default")
      (node (ref "CH9141") (pin "24") (pinfunction "SLEEP_24") (pintype "unspecified"))
      (node (ref "U1") (pin "57") (pinfunction "PB5_57") (pintype "unspecified"))
      (node (ref "U6") (pin "2") (pinfunction "SLEEP_2") (pintype "unspecified"))
    )
    (net (code "39") (name "ch9141tx") (class "Default")
      (node (ref "CH9141") (pin "15") (pinfunction "RXD_15") (pintype "unspecified"))
      (node (ref "U1") (pin "62") (pinfunction "PB9_62") (pintype "unspecified"))
      (node (ref "U6") (pin "11") (pinfunction "RXD_11") (pintype "unspecified"))
    )
    (net (code "40") (name "data0") (class "Default")
      (node (ref "FPC1") (pin "8") (pinfunction "8_8") (pintype "unspecified"))
      (node (ref "U1") (pin "14") (pinfunction "PA0-WKUP_14") (pintype "unspecified"))
    )
    (net (code "41") (name "data1") (class "Default")
      (node (ref "FPC1") (pin "9") (pinfunction "9_9") (pintype "unspecified"))
      (node (ref "U1") (pin "15") (pinfunction "PA1_15") (pintype "unspecified"))
    )
    (net (code "42") (name "data2") (class "Default")
      (node (ref "FPC1") (pin "10") (pinfunction "10_10") (pintype "unspecified"))
      (node (ref "U1") (pin "16") (pinfunction "PA2_16") (pintype "unspecified"))
    )
    (net (code "43") (name "data3") (class "Default")
      (node (ref "FPC1") (pin "11") (pinfunction "11_11") (pintype "unspecified"))
      (node (ref "U1") (pin "17") (pinfunction "PA3_17") (pintype "unspecified"))
    )
    (net (code "44") (name "data4") (class "Default")
      (node (ref "FPC1") (pin "12") (pinfunction "12_12") (pintype "unspecified"))
      (node (ref "U1") (pin "20") (pinfunction "PA4_20") (pintype "unspecified"))
    )
    (net (code "45") (name "data5") (class "Default")
      (node (ref "FPC1") (pin "13") (pinfunction "13_13") (pintype "unspecified"))
      (node (ref "U1") (pin "21") (pinfunction "PA5_21") (pintype "unspecified"))
    )
    (net (code "46") (name "data6") (class "Default")
      (node (ref "FPC1") (pin "14") (pinfunction "14_14") (pintype "unspecified"))
      (node (ref "U1") (pin "22") (pinfunction "PA6_22") (pintype "unspecified"))
    )
    (net (code "47") (name "data7") (class "Default")
      (node (ref "FPC1") (pin "15") (pinfunction "15_15") (pintype "unspecified"))
      (node (ref "U1") (pin "23") (pinfunction "PA7_23") (pintype "unspecified"))
    )
    (net (code "48") (name "dc") (class "Default")
      (node (ref "SCREEN1") (pin "6") (pinfunction "6_6") (pintype "input"))
      (node (ref "U1") (pin "36") (pinfunction "PB15_36") (pintype "unspecified"))
    )
    (net (code "49") (name "down") (class "Default")
      (node (ref "C15") (pin "2") (pinfunction "2_2") (pintype "unspecified"))
      (node (ref "SW2") (pin "4") (pinfunction "4_4") (pintype "input"))
      (node (ref "U1") (pin "50") (pinfunction "PA15_50") (pintype "unspecified"))
    )
    (net (code "50") (name "hc244oe") (class "Default")
      (node (ref "U1") (pin "41") (pinfunction "PA8_41") (pintype "unspecified"))
      (node (ref "U3") (pin "1") (pinfunction "1OE#_1") (pintype "unspecified"))
    )
    (net (code "51") (name "href") (class "Default")
      (node (ref "FPC1") (pin "5") (pinfunction "5_5") (pintype "unspecified"))
      (node (ref "U1") (pin "19") (pinfunction "PD5_19") (pintype "unspecified"))
    )
    (net (code "52") (name "led") (class "Default")
      (node (ref "Q2") (pin "2") (pinfunction "B_2") (pintype "input"))
      (node (ref "U1") (pin "45") (pinfunction "PA12_45") (pintype "unspecified"))
    )
    (net (code "53") (name "left") (class "Default")
      (node (ref "C18") (pin "2") (pinfunction "2_2") (pintype "unspecified"))
      (node (ref "SW2") (pin "2") (pinfunction "2_2") (pintype "input"))
      (node (ref "U1") (pin "53") (pinfunction "PC12_53") (pintype "unspecified"))
    )
    (net (code "54") (name "mid") (class "Default")
      (node (ref "C14") (pin "2") (pinfunction "2_2") (pintype "unspecified"))
      (node (ref "SW2") (pin "3") (pinfunction "3_3") (pintype "input"))
      (node (ref "U1") (pin "51") (pinfunction "PC10_51") (pintype "unspecified"))
    )
    (net (code "55") (name "mosi") (class "Default")
      (node (ref "SCREEN1") (pin "4") (pinfunction "4_4") (pintype "input"))
      (node (ref "U1") (pin "34") (pinfunction "PB13_34") (pintype "unspecified"))
    )
    (net (code "56") (name "motor0") (class "Default")
      (node (ref "U1") (pin "37") (pinfunction "PC6_37") (pintype "unspecified"))
      (node (ref "U3") (pin "2") (pinfunction "1A0_2") (pintype "unspecified"))
    )
    (net (code "57") (name "motor1") (class "Default")
      (node (ref "U1") (pin "38") (pinfunction "PC7_38") (pintype "unspecified"))
      (node (ref "U3") (pin "4") (pinfunction "1A1_4") (pintype "unspecified"))
    )
    (net (code "58") (name "motor2") (class "Default")
      (node (ref "U1") (pin "39") (pinfunction "PC8_39") (pintype "unspecified"))
      (node (ref "U3") (pin "6") (pinfunction "1A2_6") (pintype "unspecified"))
    )
    (net (code "59") (name "motor3") (class "Default")
      (node (ref "U1") (pin "40") (pinfunction "PC9_40") (pintype "unspecified"))
      (node (ref "U3") (pin "8") (pinfunction "1A3_8") (pintype "unspecified"))
    )
    (net (code "60") (name "mpu6050int") (class "Default")
      (node (ref "6050") (pin "8") (pinfunction "8_8") (pintype "unspecified"))
      (node (ref "U1") (pin "28") (pinfunction "PB2_28") (pintype "unspecified"))
      (node (ref "U4") (pin "12") (pinfunction "INT_12") (pintype "unspecified"))
    )
    (net (code "61") (name "oled_reset") (class "Default")
      (node (ref "SCREEN1") (pin "5") (pinfunction "5_5") (pintype "input"))
      (node (ref "U1") (pin "42") (pinfunction "PA9_42") (pintype "unspecified"))
    )
    (net (code "62") (name "pclk") (class "Default")
      (node (ref "FPC1") (pin "1") (pinfunction "1_1") (pintype "unspecified"))
      (node (ref "U1") (pin "26") (pinfunction "PB0_26") (pintype "unspecified"))
    )
    (net (code "63") (name "right") (class "Default")
      (node (ref "C16") (pin "2") (pinfunction "2_2") (pintype "unspecified"))
      (node (ref "SW2") (pin "5") (pinfunction "5_5") (pintype "input"))
      (node (ref "U1") (pin "52") (pinfunction "PC11_52") (pintype "unspecified"))
    )
    (net (code "64") (name "rld") (class "Default")
      (node (ref "CH9141") (pin "23") (pinfunction "RELOAD/LED_23") (pintype "unspecified"))
      (node (ref "R1") (pin "1") (pinfunction "1_1") (pintype "unspecified"))
      (node (ref "U6") (pin "1") (pinfunction "RELOAD/LED_1") (pintype "unspecified"))
    )
    (net (code "65") (name "rst") (class "Default")
      (node (ref "C3") (pin "2") (pinfunction "2_2") (pintype "unspecified"))
      (node (ref "R3") (pin "2") (pinfunction "2_2") (pintype "unspecified"))
      (node (ref "SW1") (pin "1") (pinfunction "1_1") (pintype "unspecified"))
      (node (ref "SW1") (pin "2") (pinfunction "2_2") (pintype "unspecified"))
      (node (ref "U1") (pin "7") (pinfunction "nRST_7") (pintype "unspecified"))
    )
    (net (code "66") (name "rst#") (class "Default")
      (node (ref "CH9141") (pin "16") (pinfunction "RST#_16") (pintype "unspecified"))
      (node (ref "U1") (pin "56") (pinfunction "PB4_56") (pintype "unspecified"))
      (node (ref "U6") (pin "12") (pinfunction "RST_12") (pintype "unspecified"))
    )
    (net (code "67") (name "rx") (class "Default")
      (node (ref "FPC1") (pin "4") (pinfunction "4_4") (pintype "unspecified"))
      (node (ref "U1") (pin "24") (pinfunction "PC4_24") (pintype "unspecified"))
    )
    (net (code "68") (name "scl") (class "Default")
      (node (ref "6050") (pin "3") (pinfunction "3_3") (pintype "unspecified"))
      (node (ref "R6") (pin "1") (pinfunction "1_1") (pintype "unspecified"))
      (node (ref "U1") (pin "29") (pinfunction "PB10_29") (pintype "unspecified"))
      (node (ref "U4") (pin "23") (pinfunction "SCL_23") (pintype "unspecified"))
    )
    (net (code "69") (name "sclk") (class "Default")
      (node (ref "SCREEN1") (pin "3") (pinfunction "3_3") (pintype "input"))
      (node (ref "U1") (pin "35") (pinfunction "PB14_35") (pintype "unspecified"))
    )
    (net (code "70") (name "sda") (class "Default")
      (node (ref "6050") (pin "4") (pinfunction "4_4") (pintype "unspecified"))
      (node (ref "R5") (pin "1") (pinfunction "1_1") (pintype "unspecified"))
      (node (ref "U1") (pin "30") (pinfunction "PB11_30") (pintype "unspecified"))
      (node (ref "U4") (pin "24") (pinfunction "SDA_24") (pintype "unspecified"))
    )
    (net (code "71") (name "ss") (class "Default")
      (node (ref "SCREEN1") (pin "7") (pinfunction "7_7") (pintype "input"))
      (node (ref "U1") (pin "33") (pinfunction "PB12_33") (pintype "unspecified"))
    )
    (net (code "72") (name "tx") (class "Default")
      (node (ref "FPC1") (pin "3") (pinfunction "3_3") (pintype "unspecified"))
      (node (ref "U1") (pin "25") (pinfunction "PC5_25") (pintype "unspecified"))
    )
    (net (code "73") (name "unconnected-(6050-Pad5)") (class "Default")
      (node (ref "6050") (pin "5") (pinfunction "5_5") (pintype "unspecified+no_connect"))
    )
    (net (code "74") (name "unconnected-(6050-Pad6)") (class "Default")
      (node (ref "6050") (pin "6") (pinfunction "6_6") (pintype "unspecified+no_connect"))
    )
    (net (code "75") (name "unconnected-(CH9141-ADC-Pad7)") (class "Default")
      (node (ref "CH9141") (pin "7") (pinfunction "ADC_7") (pintype "unspecified+no_connect"))
    )
    (net (code "76") (name "unconnected-(CH9141-CTS#-Pad13)") (class "Default")
      (node (ref "CH9141") (pin "13") (pinfunction "CTS#_13") (pintype "unspecified+no_connect"))
    )
    (net (code "77") (name "unconnected-(CH9141-DCD#{slash}GPIO7-Pad8)") (class "Default")
      (node (ref "CH9141") (pin "8") (pinfunction "DCD#/GPIO7_8") (pintype "unspecified+no_connect"))
    )
    (net (code "78") (name "unconnected-(CH9141-DSR#{slash}GPIO6-Pad9)") (class "Default")
      (node (ref "CH9141") (pin "9") (pinfunction "DSR#/GPIO6_9") (pintype "unspecified+no_connect"))
    )
    (net (code "79") (name "unconnected-(CH9141-DTR#{slash}BLESTA{slash}GPIO4-Pad11)") (class "Default")
      (node (ref "CH9141") (pin "11") (pinfunction "DTR#/BLESTA/GPIO4_11") (pintype "unspecified+no_connect"))
    )
    (net (code "80") (name "unconnected-(CH9141-GPIO0-Pad28)") (class "Default")
      (node (ref "CH9141") (pin "28") (pinfunction "GPIO0_28") (pintype "unspecified+no_connect"))
    )
    (net (code "81") (name "unconnected-(CH9141-GPIO1-Pad27)") (class "Default")
      (node (ref "CH9141") (pin "27") (pinfunction "GPIO1_27") (pintype "unspecified+no_connect"))
    )
    (net (code "82") (name "unconnected-(CH9141-GPIO2-Pad26)") (class "Default")
      (node (ref "CH9141") (pin "26") (pinfunction "GPIO2_26") (pintype "unspecified+no_connect"))
    )
    (net (code "83") (name "unconnected-(CH9141-GPIO3-Pad25)") (class "Default")
      (node (ref "CH9141") (pin "25") (pinfunction "GPIO3_25") (pintype "unspecified+no_connect"))
    )
    (net (code "84") (name "unconnected-(CH9141-NC-Pad17)") (class "Default")
      (node (ref "CH9141") (pin "17") (pinfunction "NC_17") (pintype "unspecified+no_connect"))
    )
    (net (code "85") (name "unconnected-(CH9141-RI#{slash}GPIO5-Pad10)") (class "Default")
      (node (ref "CH9141") (pin "10") (pinfunction "RI#/GPIO5_10") (pintype "unspecified+no_connect"))
    )
    (net (code "86") (name "unconnected-(CH9141-RTS#{slash}TNOW-Pad12)") (class "Default")
      (node (ref "CH9141") (pin "12") (pinfunction "RTS#/TNOW_12") (pintype "unspecified+no_connect"))
    )
    (net (code "87") (name "unconnected-(CH9141-VSW-Pad4)") (class "Default")
      (node (ref "CH9141") (pin "4") (pinfunction "VSW_4") (pintype "unspecified+no_connect"))
    )
    (net (code "88") (name "unconnected-(FPC1-Pad19)") (class "Default")
      (node (ref "FPC1") (pin "19") (pinfunction "19_19") (pintype "unspecified+no_connect"))
    )
    (net (code "89") (name "unconnected-(FPC1-Pad20)") (class "Default")
      (node (ref "FPC1") (pin "20") (pinfunction "20_20") (pintype "unspecified+no_connect"))
    )
    (net (code "90") (name "unconnected-(J2-Pad5)") (class "Default")
      (node (ref "J2") (pin "5") (pinfunction "5_5") (pintype "unspecified+no_connect"))
    )
    (net (code "91") (name "unconnected-(J2-Pad6)") (class "Default")
      (node (ref "J2") (pin "6") (pinfunction "6_6") (pintype "unspecified+no_connect"))
    )
    (net (code "92") (name "unconnected-(J3-Pad5)") (class "Default")
      (node (ref "J3") (pin "5") (pinfunction "5_5") (pintype "unspecified+no_connect"))
    )
    (net (code "93") (name "unconnected-(J3-Pad6)") (class "Default")
      (node (ref "J3") (pin "6") (pinfunction "6_6") (pintype "unspecified+no_connect"))
    )
    (net (code "94") (name "unconnected-(P1-Pad2)") (class "Default")
      (node (ref "P1") (pin "2") (pinfunction "2_2") (pintype "unspecified+no_connect"))
    )
    (net (code "95") (name "unconnected-(P1-Pad7)") (class "Default")
      (node (ref "P1") (pin "7") (pinfunction "7_7") (pintype "unspecified+no_connect"))
    )
    (net (code "96") (name "unconnected-(P1-Pad8)") (class "Default")
      (node (ref "P1") (pin "8") (pinfunction "8_8") (pintype "unspecified+no_connect"))
    )
    (net (code "97") (name "unconnected-(U1-PB1-Pad27)") (class "Default")
      (node (ref "U1") (pin "27") (pinfunction "PB1_27") (pintype "unspecified+no_connect"))
    )
    (net (code "98") (name "unconnected-(U1-PC2-Pad10)") (class "Default")
      (node (ref "U1") (pin "10") (pinfunction "PC2_10") (pintype "unspecified+no_connect"))
    )
    (net (code "99") (name "unconnected-(U1-PC3-Pad11)") (class "Default")
      (node (ref "U1") (pin "11") (pinfunction "PC3_11") (pintype "unspecified+no_connect"))
    )
    (net (code "100") (name "unconnected-(U1-PC13-Pad2)") (class "Default")
      (node (ref "U1") (pin "2") (pinfunction "PC13_2") (pintype "unspecified+no_connect"))
    )
    (net (code "101") (name "unconnected-(U1-PC14-Pad3)") (class "Default")
      (node (ref "U1") (pin "3") (pinfunction "PC14_3") (pintype "unspecified+no_connect"))
    )
    (net (code "102") (name "unconnected-(U1-PC15-Pad4)") (class "Default")
      (node (ref "U1") (pin "4") (pinfunction "PC15_4") (pintype "unspecified+no_connect"))
    )
    (net (code "103") (name "unconnected-(U1-PD2-Pad47)") (class "Default")
      (node (ref "U1") (pin "47") (pinfunction "PD2_47") (pintype "unspecified+no_connect"))
    )
    (net (code "104") (name "unconnected-(U1-PD3-Pad48)") (class "Default")
      (node (ref "U1") (pin "48") (pinfunction "PD3_48") (pintype "unspecified+no_connect"))
    )
    (net (code "105") (name "unconnected-(U1-PD7-Pad1)") (class "Default")
      (node (ref "U1") (pin "1") (pinfunction "PD7_1") (pintype "unspecified+no_connect"))
    )
    (net (code "106") (name "unconnected-(U2-Pad3)") (class "Default")
      (node (ref "U2") (pin "3") (pinfunction "3_3") (pintype "unspecified+no_connect"))
    )
    (net (code "107") (name "unconnected-(U3-2A0-Pad17)") (class "Default")
      (node (ref "U3") (pin "17") (pinfunction "2A0_17") (pintype "unspecified+no_connect"))
    )
    (net (code "108") (name "unconnected-(U3-2A1-Pad15)") (class "Default")
      (node (ref "U3") (pin "15") (pinfunction "2A1_15") (pintype "unspecified+no_connect"))
    )
    (net (code "109") (name "unconnected-(U3-2A2-Pad13)") (class "Default")
      (node (ref "U3") (pin "13") (pinfunction "2A2_13") (pintype "unspecified+no_connect"))
    )
    (net (code "110") (name "unconnected-(U3-2A3-Pad11)") (class "Default")
      (node (ref "U3") (pin "11") (pinfunction "2A3_11") (pintype "unspecified+no_connect"))
    )
    (net (code "111") (name "unconnected-(U3-2OE#-Pad19)") (class "Default")
      (node (ref "U3") (pin "19") (pinfunction "2OE#_19") (pintype "unspecified+no_connect"))
    )
    (net (code "112") (name "unconnected-(U3-2Y0-Pad3)") (class "Default")
      (node (ref "U3") (pin "3") (pinfunction "2Y0_3") (pintype "unspecified+no_connect"))
    )
    (net (code "113") (name "unconnected-(U3-2Y1-Pad5)") (class "Default")
      (node (ref "U3") (pin "5") (pinfunction "2Y1_5") (pintype "unspecified+no_connect"))
    )
    (net (code "114") (name "unconnected-(U3-2Y2-Pad7)") (class "Default")
      (node (ref "U3") (pin "7") (pinfunction "2Y2_7") (pintype "unspecified+no_connect"))
    )
    (net (code "115") (name "unconnected-(U3-2Y3-Pad9)") (class "Default")
      (node (ref "U3") (pin "9") (pinfunction "2Y3_9") (pintype "unspecified+no_connect"))
    )
    (net (code "116") (name "unconnected-(U4-AUX_CL-Pad7)") (class "Default")
      (node (ref "U4") (pin "7") (pinfunction "AUX_CL_7") (pintype "unspecified+no_connect"))
    )
    (net (code "117") (name "unconnected-(U4-AUX_DA-Pad6)") (class "Default")
      (node (ref "U4") (pin "6") (pinfunction "AUX_DA_6") (pintype "unspecified+no_connect"))
    )
    (net (code "118") (name "unconnected-(U4-NC-Pad2)") (class "Default")
      (node (ref "U4") (pin "2") (pinfunction "NC_2") (pintype "unspecified+no_connect"))
    )
    (net (code "119") (name "unconnected-(U4-NC-Pad3)") (class "Default")
      (node (ref "U4") (pin "3") (pinfunction "NC_3") (pintype "unspecified+no_connect"))
    )
    (net (code "120") (name "unconnected-(U4-NC-Pad4)") (class "Default")
      (node (ref "U4") (pin "4") (pinfunction "NC_4") (pintype "unspecified+no_connect"))
    )
    (net (code "121") (name "unconnected-(U4-NC-Pad5)") (class "Default")
      (node (ref "U4") (pin "5") (pinfunction "NC_5") (pintype "unspecified+no_connect"))
    )
    (net (code "122") (name "unconnected-(U4-NC-Pad14)") (class "Default")
      (node (ref "U4") (pin "14") (pinfunction "NC_14") (pintype "unspecified+no_connect"))
    )
    (net (code "123") (name "unconnected-(U4-NC-Pad15)") (class "Default")
      (node (ref "U4") (pin "15") (pinfunction "NC_15") (pintype "unspecified+no_connect"))
    )
    (net (code "124") (name "unconnected-(U4-NC-Pad16)") (class "Default")
      (node (ref "U4") (pin "16") (pinfunction "NC_16") (pintype "unspecified+no_connect"))
    )
    (net (code "125") (name "unconnected-(U4-NC-Pad17)") (class "Default")
      (node (ref "U4") (pin "17") (pinfunction "NC_17") (pintype "unspecified+no_connect"))
    )
    (net (code "126") (name "unconnected-(U4-RESV-Pad19)") (class "Default")
      (node (ref "U4") (pin "19") (pinfunction "RESV_19") (pintype "unspecified+no_connect"))
    )
    (net (code "127") (name "unconnected-(U4-RESV-Pad21)") (class "Default")
      (node (ref "U4") (pin "21") (pinfunction "RESV_21") (pintype "unspecified+no_connect"))
    )
    (net (code "128") (name "unconnected-(U4-RESV-Pad22)") (class "Default")
      (node (ref "U4") (pin "22") (pinfunction "RESV_22") (pintype "unspecified+no_connect"))
    )
    (net (code "129") (name "unconnected-(U6-DSR{slash}GPIO6-Pad8)") (class "Default")
      (node (ref "U6") (pin "8") (pinfunction "DSR/GPIO6_8") (pintype "unspecified+no_connect"))
    )
    (net (code "130") (name "unconnected-(U6-DTR{slash}GPIO4-Pad9)") (class "Default")
      (node (ref "U6") (pin "9") (pinfunction "DTR/GPIO4_9") (pintype "unspecified+no_connect"))
    )
    (net (code "131") (name "unconnected-(U6-GPIO0-Pad4)") (class "Default")
      (node (ref "U6") (pin "4") (pinfunction "GPIO0_4") (pintype "unspecified+no_connect"))
    )
    (net (code "132") (name "unconnected-(U6-GPIO1-Pad3)") (class "Default")
      (node (ref "U6") (pin "3") (pinfunction "GPIO1_3") (pintype "unspecified+no_connect"))
    )
    (net (code "133") (name "unconnected-(X1-GND-Pad2)") (class "Default")
      (node (ref "X1") (pin "2") (pinfunction "GND_2") (pintype "input+no_connect"))
    )
    (net (code "134") (name "unconnected-(X1-GND-Pad4)") (class "Default")
      (node (ref "X1") (pin "4") (pinfunction "GND_4") (pintype "input+no_connect"))
    )
    (net (code "135") (name "up") (class "Default")
      (node (ref "C17") (pin "2") (pinfunction "2_2") (pintype "unspecified"))
      (node (ref "SW2") (pin "6") (pinfunction "6_6") (pintype "input"))
      (node (ref "U1") (pin "54") (pinfunction "PD6_54") (pintype "unspecified"))
    )
    (net (code "136") (name "vsync") (class "Default")
      (node (ref "FPC1") (pin "6") (pinfunction "6_6") (pintype "unspecified"))
      (node (ref "U1") (pin "18") (pinfunction "PD4_18") (pintype "unspecified"))
    )
  )
)
